# 5V_Buck.net
KiCad netlist of a schematic drawn in Altium Designer
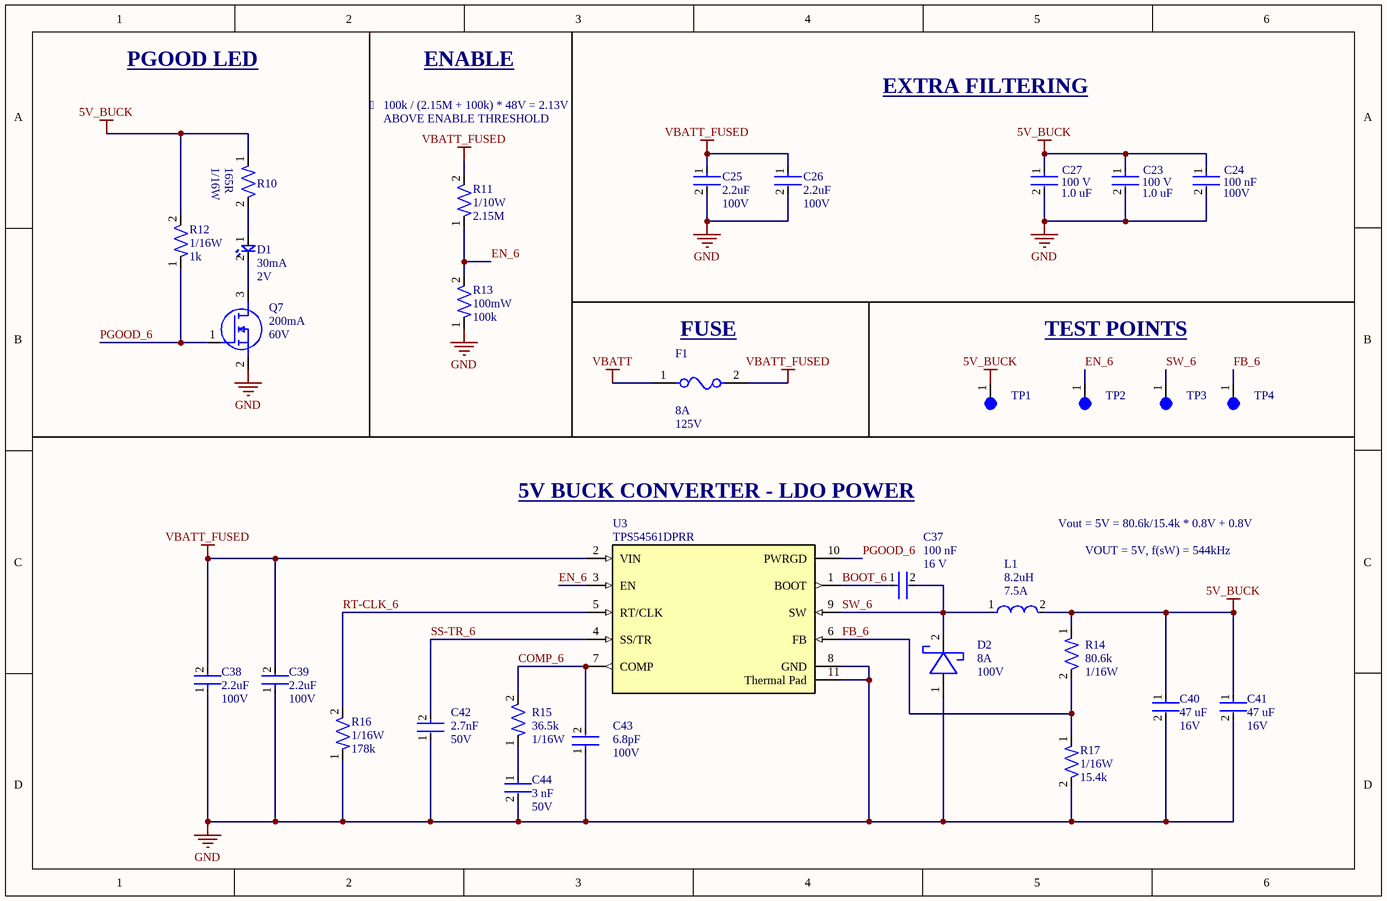
[diagram p0: 5V_Buck.SchDoc]

(export (version "E")
  (design (tool "Eeschema 10.0.6"))
  (components
    (comp (ref "C23")
      (value "08051C105K4Z2A")
      (footprint "CAP-0805")
      (description "CAP CER 1UF 50V X7R 0805")
      (fields (field (name "VOLTAGE") "100 V") (field (name "CAPACITANCE") "1.0 uF"))
      (libsource (lib "JLC_25") (part "CAP-1U-0001"))
    )
    (comp (ref "C24")
      (value "GRM188R72A104KA35D")
      (footprint "CAP-0603")
      (description "CAP CER 100NF 100V X7R 0603")
      (fields (field (name "CAPACITANCE") "100 nF") (field (name "VOLTAGE") "100V"))
      (libsource (lib "JLC_25") (part "CAP-1U-0002"))
    )
    (comp (ref "C25")
      (value "CC1206KKX7R0BB225")
      (footprint "CAP-1206")
      (description "CAP CER 2.2UF 100V X7R 1206")
      (fields (field (name "CAPACITANCE") "2.2uF") (field (name "VOLTAGE") "100V"))
      (libsource (lib "JLC_25") (part "CAP-2.2U-0001"))
    )
    (comp (ref "C26")
      (value "CC1206KKX7R0BB225")
      (footprint "CAP-1206")
      (description "CAP CER 2.2UF 100V X7R 1206")
      (fields (field (name "CAPACITANCE") "2.2uF") (field (name "VOLTAGE") "100V"))
      (libsource (lib "JLC_25") (part "CAP-2.2U-0001"))
    )
    (comp (ref "C27")
      (value "08051C105K4Z2A")
      (footprint "CAP-0805")
      (description "CAP CER 1UF 50V X7R 0805")
      (fields (field (name "VOLTAGE") "100 V") (field (name "CAPACITANCE") "1.0 uF"))
      (libsource (lib "JLC_25") (part "CAP-1U-0001"))
    )
    (comp (ref "C37")
      (value "CC0402KRX7R7BB104")
      (footprint "CAP-0402")
      (description "CAP CER 0.1UF 16V X7R 0402")
      (fields (field (name "VOLTAGE RATING") "16 V") (field (name "CAPACITANCE") "100 nF"))
      (libsource (lib "JLC_25") (part "CAP-0.1U-0001"))
    )
    (comp (ref "C38")
      (value "CC1206KKX7R0BB225")
      (footprint "CAP-1206")
      (description "CAP CER 2.2UF 100V X7R 1206")
      (fields (field (name "CAPACITANCE") "2.2uF") (field (name "VOLTAGE") "100V"))
      (libsource (lib "JLC_25") (part "CAP-2.2U-0001"))
    )
    (comp (ref "C39")
      (value "CC1206KKX7R0BB225")
      (footprint "CAP-1206")
      (description "CAP CER 2.2UF 100V X7R 1206")
      (fields (field (name "CAPACITANCE") "2.2uF") (field (name "VOLTAGE") "100V"))
      (libsource (lib "JLC_25") (part "CAP-2.2U-0001"))
    )
    (comp (ref "C40")
      (value "GRM32ER61C476KE15L")
      (footprint "MasterLib:CAP-1210")
      (description "CAP CER 47UF 16V X5R 1210")
      (fields (field (name "CAPACITANCE") "47 uF") (field (name "VOLTAGE") "16V"))
      (libsource (lib "JLC_25") (part "CAP-47U-0002"))
    )
    (comp (ref "C41")
      (value "GRM32ER61C476KE15L")
      (footprint "MasterLib:CAP-1210")
      (description "CAP CER 47UF 16V X5R 1210")
      (fields (field (name "CAPACITANCE") "47 uF") (field (name "VOLTAGE") "16V"))
      (libsource (lib "JLC_25") (part "CAP-47U-0002"))
    )
    (comp (ref "C42")
      (value "GRM2165C1H272JA01D")
      (footprint "CAP-0805")
      (description "CAP CER 2700PF 50V C0G/NP0 0805")
      (fields (field (name "VOLTAGE") "50V") (field (name "CAPACITANCE") "2.7nF"))
      (libsource (lib "JLC_25") (part "CAP-2.7N-0001"))
    )
    (comp (ref "C43")
      (value "CC0603CRNPO0BN6R8")
      (footprint "CAP-0603")
      (description "CAP CER 6.8PF 100V C0G/NPO 0603")
      (fields (field (name "VOLTAGE") "100V") (field (name "CAPACITANCE") "6.8pF"))
      (libsource (lib "JLC_25") (part "CAP-6.8P-0001"))
    )
    (comp (ref "C44")
      (value "GRM1885C1H302JA01D")
      (footprint "CAP-0603")
      (description "3000 pF ±5% 50V Ceramic Capacitor C0G, NP0 0603 (1608 Metric)")
      (fields (field (name "VOLTAGE") "50V") (field (name "CAPACITANCE") "3 nF"))
      (libsource (lib "JLC_25") (part "CAP-3N-0001"))
    )
    (comp (ref "D1")
      (value "BL-HKC36G-AV-TRB")
      (footprint "LED-0603")
      (description "LED YELLOW CLEAR 0603 SMD")
      (fields (field (name "FORWARD CURRENT") "30mA") (field (name "FORWARD VOLTAGE") "2V"))
      (libsource (lib "JLC_25") (part "LED-0001"))
    )
    (comp (ref "D2")
      (value "SDT8A100P5-7")
      (footprint "DO-POWERDI5")
      (description "DIODE SCHOTTKY 100V 8A POWERDI5")
      (fields (field (name "FORWARD CURRENT") "8A") (field (name "REVERSE VOLTAGE (DC)") "100V"))
      (libsource (lib "JLC_25") (part "DIO-SCHOTTKY-0001"))
    )
    (comp (ref "F1")
      (value "01550900M")
      (footprint "FUSE-0001")
      (description "FUSE BLOK CARTRIDGE 125V 10A SMD")
      (fields (field (name "FUSE CURRENT") "8A") (field (name "VOLTAGE RATING") "125V"))
      (libsource (lib "JLC_25") (part "FUSE-0001"))
    )
    (comp (ref "L1")
      (value "IHLP2525CZER8R2M01")
      (footprint "IND25X25CZ")
      (description "8.2 µH Shielded Molded Inductor 4 A 68mOhm Max Nonstandard")
      (fields (field (name "INDUCTANCE") "8.2uH") (field (name "CURRENT RATING") "7.5A"))
      (libsource (lib "JLC_25") (part "IND-8.2U-0001"))
    )
    (comp (ref "Q7")
      (value "T2N7002AK,LM")
      (footprint "IC-SOT23-3")
      (description "MOSFET N-CH 60V 200MA SOT23")
      (fields (field (name "CONTINUOUS CURRENT") "200mA") (field (name "VOLTAGE") "60V"))
      (libsource (lib "JLC_25") (part "NMOS-200MA-0001"))
    )
    (comp (ref "R10")
      (value "RC0402FR-07165RL")
      (footprint "RES-0402")
      (description "RES 165 OHM 1% 1/16W 0402")
      (libsource (lib "JLC_25") (part "RES-165-0001"))
    )
    (comp (ref "R11")
      (value "RC0603FR-072M15L")
      (footprint "RES-0603")
      (description "RES SMD 2.15M OHM 1% 1/10W 0603")
      (fields
        (field (name "TOLERANCE") "1%")
        (field (name "POWER") "1/10W")
        (field (name "RESISTANCE") "2.15M")
      )
      (libsource (lib "JLC_25") (part "RES-2.15M-0001"))
    )
    (comp (ref "R12")
      (value "RC0402FR-071KL")
      (footprint "RES-0402")
      (description "RES 1K OHM 1% 1/16W 0402")
      (fields (field (name "TOLERANCE") "1%") (field (name "POWER") "1/16W") (field (name "RESISTANCE") "1k"))
      (libsource (lib "JLC_25") (part "RES-1k-0001"))
    )
    (comp (ref "R13")
      (value "RC0603FR-07100KL")
      (footprint "RES-0603")
      (description "RES SMD 100K OHM 1% 1/10W 0603")
      (fields
        (field (name "TOLERANCE") "1%")
        (field (name "POWER") "100mW")
        (field (name "RESISTANCE") "100k")
      )
      (libsource (lib "JLC_25") (part "RES-100k-0001"))
    )
    (comp (ref "R14")
      (value "RC0402FR-0780K6L")
      (footprint "RES-0402")
      (description "80.6 kOhms ±1% 0.063W, 1/16W Chip Resistor 0402 (1005 Metric) Moisture Resistant Thick Film")
      (fields
        (field (name "TOLERANCE") "1%")
        (field (name "RESISTANCE") "80.6k")
        (field (name "POWER") "1/16W")
      )
      (libsource (lib "JLC_25") (part "RES-80.6k-0001"))
    )
    (comp (ref "R15")
      (value "RC0402FR-0736K5L")
      (footprint "RES-0402")
      (description "36.5 kOhms ±1% 0.063W, 1/16W Chip Resistor 0402 (1005 Metric) Moisture Resistant Thick Film")
      (fields (field (name "POWER") "1/16W") (field (name "RESISTANCE") "36.5k"))
      (libsource (lib "JLC_25") (part "RES-36.5k-0001"))
    )
    (comp (ref "R16")
      (value "RTT021783FTH")
      (footprint "RES-0402")
      (description "62.5mW Thick Film Resistors 50V ±100ppm/℃ ±1% 178kΩ 0402 Chip Resistor - Surface Mount ROHS")
      (fields
        (field (name "TOLERANCE") "1%")
        (field (name "POWER") "1/16W")
        (field (name "RESISTANCE") "178k")
      )
      (libsource (lib "JLC_25") (part "RES-178k-0001_1"))
    )
    (comp (ref "R17")
      (value "AC0402FR-0715K4L")
      (footprint "RES-0402")
      (description "RES 15.4kΩ ±1% 0.063W 0402")
      (fields
        (field (name "TOLERANCE") "1%")
        (field (name "POWER") "1/16W")
        (field (name "RESISTANCE") "15.4k")
      )
      (libsource (lib "JLC_25") (part "RES-15.4K-0001"))
    )
    (comp (ref "TP1")
      (value "5003")
      (footprint "TEST-POINT-0001")
      (description "Oranange PC Test Point, Miniature Phoisphor Bronze Silver Plating Through Hole Mounting Type")
      (libsource (lib "*") (part "TEST-POINT-0001"))
    )
    (comp (ref "TP2")
      (value "5003")
      (footprint "TEST-POINT-0001")
      (description "Oranange PC Test Point, Miniature Phoisphor Bronze Silver Plating Through Hole Mounting Type")
      (libsource (lib "*") (part "TEST-POINT-0001"))
    )
    (comp (ref "TP3")
      (value "5003")
      (footprint "TEST-POINT-0001")
      (description "Oranange PC Test Point, Miniature Phoisphor Bronze Silver Plating Through Hole Mounting Type")
      (libsource (lib "*") (part "TEST-POINT-0001"))
    )
    (comp (ref "TP4")
      (value "5003")
      (footprint "TEST-POINT-0001")
      (description "Oranange PC Test Point, Miniature Phoisphor Bronze Silver Plating Through Hole Mounting Type")
      (libsource (lib "*") (part "TEST-POINT-0001"))
    )
    (comp (ref "U3")
      (value "TPS54561DPRR")
      (footprint "IC-10WSON")
      (description "IC REG BUCK ADJ 5A 10WSON")
      (libsource (lib "JLC_25") (part "IC-BUCK-0001"))
    )
  )
  (nets
    (net (code "1") (name "/BOOT_6") (class "Default")
      (node (ref "C37") (pin "1") (pinfunction "1_1") (pintype "passive"))
      (node (ref "U3") (pin "1") (pinfunction "BOOT_1") (pintype "output"))
    )
    (net (code "2") (name "/COMP_6") (class "Default")
      (node (ref "C43") (pin "2") (pinfunction "2_2") (pintype "passive"))
      (node (ref "R15") (pin "2") (pinfunction "2_2") (pintype "passive"))
      (node (ref "U3") (pin "7") (pinfunction "COMP_7") (pintype "output"))
    )
    (net (code "3") (name "/EN_6") (class "Default")
      (node (ref "R11") (pin "1") (pinfunction "1_1") (pintype "passive"))
      (node (ref "R13") (pin "2") (pinfunction "2_2") (pintype "passive"))
      (node (ref "TP2") (pin "1") (pinfunction "0_1") (pintype "passive"))
      (node (ref "U3") (pin "3") (pinfunction "EN_3") (pintype "input"))
    )
    (net (code "4") (name "/FB_6") (class "Default")
      (node (ref "R14") (pin "2") (pinfunction "2_2") (pintype "passive"))
      (node (ref "R17") (pin "1") (pinfunction "1_1") (pintype "passive"))
      (node (ref "TP4") (pin "1") (pinfunction "0_1") (pintype "passive"))
      (node (ref "U3") (pin "6") (pinfunction "FB_6") (pintype "input"))
    )
    (net (code "5") (name "/PGOOD_6") (class "Default")
      (node (ref "Q7") (pin "1") (pinfunction "G_1") (pintype "passive"))
      (node (ref "R12") (pin "1") (pinfunction "1_1") (pintype "passive"))
      (node (ref "U3") (pin "10") (pinfunction "PWRGD_10") (pintype "open_collector"))
    )
    (net (code "6") (name "/RT-CLK_6") (class "Default")
      (node (ref "R16") (pin "2") (pinfunction "2_2") (pintype "passive"))
      (node (ref "U3") (pin "5") (pinfunction "RT/CLK_5") (pintype "input"))
    )
    (net (code "7") (name "/SS-TR_6") (class "Default")
      (node (ref "C42") (pin "2") (pinfunction "2_2") (pintype "passive"))
      (node (ref "U3") (pin "4") (pinfunction "SS/TR_4") (pintype "input"))
    )
    (net (code "8") (name "/SW_6") (class "Default")
      (node (ref "C37") (pin "2") (pinfunction "2_2") (pintype "passive"))
      (node (ref "D2") (pin "2") (pinfunction "ANODE_2") (pintype "passive"))
      (node (ref "L1") (pin "1") (pinfunction "1_1") (pintype "passive"))
      (node (ref "TP3") (pin "1") (pinfunction "0_1") (pintype "passive"))
      (node (ref "U3") (pin "9") (pinfunction "SW_9") (pintype "input"))
    )
    (net (code "9") (name "5V_BUCK") (class "Default")
      (node (ref "C23") (pin "1") (pinfunction "1_1") (pintype "passive"))
      (node (ref "C24") (pin "1") (pinfunction "1_1") (pintype "passive"))
      (node (ref "C27") (pin "1") (pinfunction "1_1") (pintype "passive"))
      (node (ref "C40") (pin "1") (pinfunction "1_1") (pintype "passive"))
      (node (ref "C41") (pin "1") (pinfunction "1_1") (pintype "passive"))
      (node (ref "L1") (pin "2") (pinfunction "2_2") (pintype "passive"))
      (node (ref "R10") (pin "1") (pinfunction "1_1") (pintype "passive"))
      (node (ref "R12") (pin "2") (pinfunction "2_2") (pintype "passive"))
      (node (ref "R14") (pin "1") (pinfunction "1_1") (pintype "passive"))
      (node (ref "TP1") (pin "1") (pinfunction "0_1") (pintype "passive"))
    )
    (net (code "10") (name "GND") (class "Default")
      (node (ref "C23") (pin "2") (pinfunction "2_2") (pintype "passive"))
      (node (ref "C24") (pin "2") (pinfunction "2_2") (pintype "passive"))
      (node (ref "C25") (pin "2") (pinfunction "2_2") (pintype "passive"))
      (node (ref "C26") (pin "2") (pinfunction "2_2") (pintype "passive"))
      (node (ref "C27") (pin "2") (pinfunction "2_2") (pintype "passive"))
      (node (ref "C38") (pin "1") (pinfunction "1_1") (pintype "passive"))
      (node (ref "C39") (pin "1") (pinfunction "1_1") (pintype "passive"))
      (node (ref "C40") (pin "2") (pinfunction "2_2") (pintype "passive"))
      (node (ref "C41") (pin "2") (pinfunction "2_2") (pintype "passive"))
      (node (ref "C42") (pin "1") (pinfunction "1_1") (pintype "passive"))
      (node (ref "C43") (pin "1") (pinfunction "1_1") (pintype "passive"))
      (node (ref "C44") (pin "2") (pinfunction "2_2") (pintype "passive"))
      (node (ref "D2") (pin "1") (pinfunction "CATHODE_1") (pintype "passive"))
      (node (ref "Q7") (pin "2") (pinfunction "S_2") (pintype "passive"))
      (node (ref "R13") (pin "1") (pinfunction "1_1") (pintype "passive"))
      (node (ref "R16") (pin "1") (pinfunction "1_1") (pintype "passive"))
      (node (ref "R17") (pin "2") (pinfunction "2_2") (pintype "passive"))
      (node (ref "U3") (pin "11") (pinfunction "Thermal_Pad_11") (pintype "power_in"))
      (node (ref "U3") (pin "8") (pinfunction "GND_8") (pintype "power_in"))
    )
    (net (code "11") (name "Net-(C44-Pad1)") (class "Default")
      (node (ref "C44") (pin "1") (pinfunction "1_1") (pintype "passive"))
      (node (ref "R15") (pin "1") (pinfunction "1_1") (pintype "passive"))
    )
    (net (code "12") (name "Net-(D1-Pad1)") (class "Default")
      (node (ref "D1") (pin "1") (pinfunction "1_1") (pintype "passive"))
      (node (ref "R10") (pin "2") (pinfunction "2_2") (pintype "passive"))
    )
    (net (code "13") (name "Net-(Q7-D)") (class "Default")
      (node (ref "D1") (pin "2") (pinfunction "2_2") (pintype "passive"))
      (node (ref "Q7") (pin "3") (pinfunction "D_3") (pintype "passive"))
    )
    (net (code "14") (name "VBATT") (class "Default")
      (node (ref "F1") (pin "1") (pinfunction "1_1") (pintype "passive"))
    )
    (net (code "15") (name "VBATT_FUSED") (class "Default")
      (node (ref "C25") (pin "1") (pinfunction "1_1") (pintype "passive"))
      (node (ref "C26") (pin "1") (pinfunction "1_1") (pintype "passive"))
      (node (ref "C38") (pin "2") (pinfunction "2_2") (pintype "passive"))
      (node (ref "C39") (pin "2") (pinfunction "2_2") (pintype "passive"))
      (node (ref "F1") (pin "2") (pinfunction "2_2") (pintype "passive"))
      (node (ref "R11") (pin "2") (pinfunction "2_2") (pintype "passive"))
      (node (ref "U3") (pin "2") (pinfunction "VIN_2") (pintype "input"))
    )
  )
)
